# digital.net
KiCad netlist of a schematic drawn in EAGLE
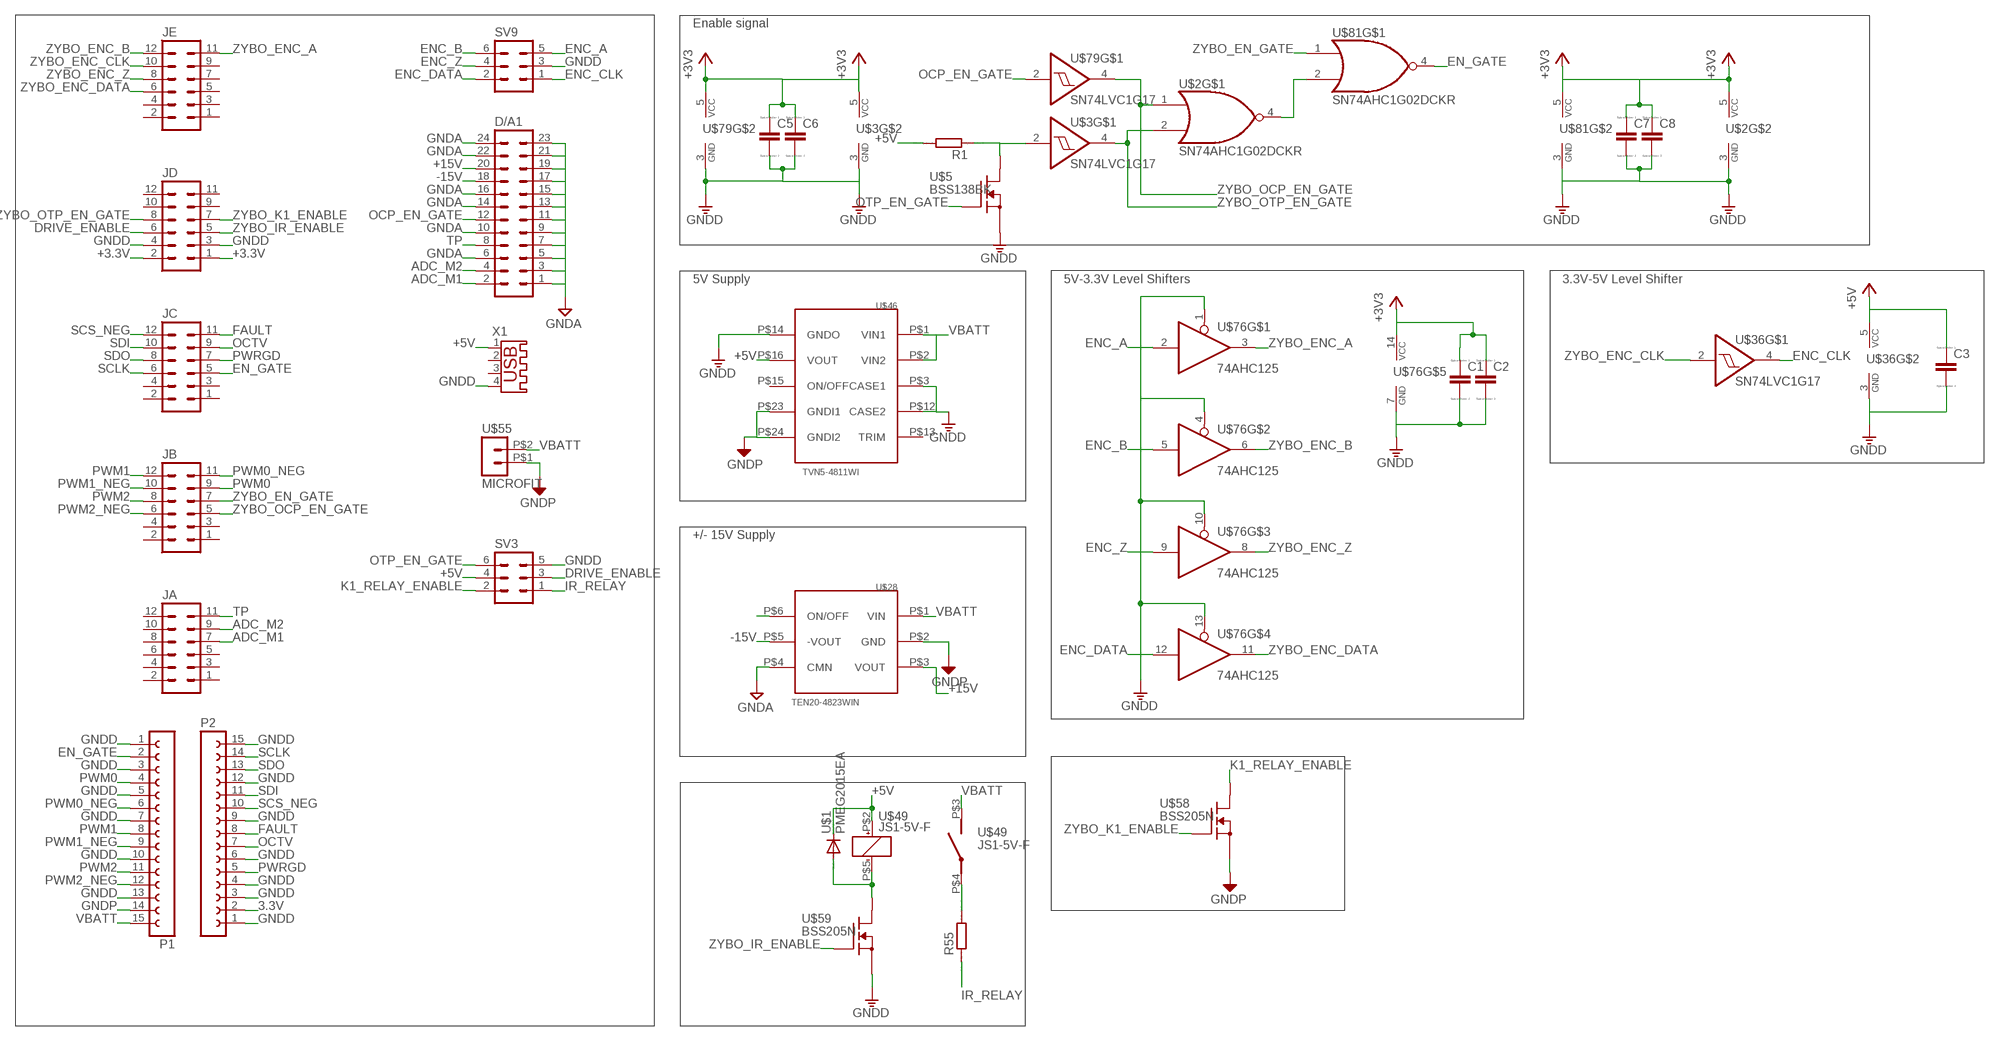
[diagram p0: schematic, sheet 1]

(export (version "E")
  (design (tool "Eeschema 10.0.6"))
  (components
    (comp (ref "C1")
      (value "CC1206")
      (footprint "eagle-import:C1206")
      (libsource (lib "eagle-import") (part "CC1206"))
    )
    (comp (ref "C2")
      (value "CC1206")
      (footprint "eagle-import:C1206")
      (libsource (lib "eagle-import") (part "CC1206"))
    )
    (comp (ref "C3")
      (value "CC1206")
      (footprint "eagle-import:C1206")
      (libsource (lib "eagle-import") (part "CC1206"))
    )
    (comp (ref "C5")
      (value "CC1206")
      (footprint "eagle-import:C1206")
      (libsource (lib "eagle-import") (part "CC1206"))
    )
    (comp (ref "C6")
      (value "CC1206")
      (footprint "eagle-import:C1206")
      (libsource (lib "eagle-import") (part "CC1206"))
    )
    (comp (ref "C7")
      (value "CC1206")
      (footprint "eagle-import:C1206")
      (libsource (lib "eagle-import") (part "CC1206"))
    )
    (comp (ref "C8")
      (value "CC1206")
      (footprint "eagle-import:C1206")
      (libsource (lib "eagle-import") (part "CC1206"))
    )
    (comp (ref "D/A1")
      (value "MA12-2")
      (footprint "eagle-import:MA12-2")
      (libsource (lib "eagle-import") (part "MA12-2"))
    )
    (comp (ref "JA")
      (value "MA06-2")
      (footprint "eagle-import:MA06-2")
      (libsource (lib "eagle-import") (part "MA06-2"))
    )
    (comp (ref "JB")
      (value "MA06-2")
      (footprint "eagle-import:MA06-2")
      (libsource (lib "eagle-import") (part "MA06-2"))
    )
    (comp (ref "JC")
      (value "MA06-2")
      (footprint "eagle-import:MA06-2")
      (libsource (lib "eagle-import") (part "MA06-2"))
    )
    (comp (ref "JD")
      (value "MA06-2")
      (footprint "eagle-import:MA06-2")
      (libsource (lib "eagle-import") (part "MA06-2"))
    )
    (comp (ref "JE")
      (value "MA06-2")
      (footprint "eagle-import:MA06-2")
      (libsource (lib "eagle-import") (part "MA06-2"))
    )
    (comp (ref "P1")
      (value "FE15-1")
      (footprint "eagle-import:FE15")
      (libsource (lib "eagle-import") (part "FE15-1"))
    )
    (comp (ref "P2")
      (value "FE15-1")
      (footprint "eagle-import:FE15")
      (libsource (lib "eagle-import") (part "FE15-1"))
    )
    (comp (ref "R1")
      (value "RR1206")
      (footprint "eagle-import:R1206")
      (libsource (lib "eagle-import") (part "RR1206"))
    )
    (comp (ref "R55")
      (value "RR1206")
      (footprint "eagle-import:R1206")
      (libsource (lib "eagle-import") (part "RR1206"))
    )
    (comp (ref "SV3")
      (value "MA03-2")
      (footprint "eagle-import:MA03-2")
      (libsource (lib "eagle-import") (part "MA03-2"))
    )
    (comp (ref "SV9")
      (value "MA03-2")
      (footprint "eagle-import:MA03-2")
      (libsource (lib "eagle-import") (part "MA03-2"))
    )
    (comp (ref "U$1")
      (value "PMEG2015EA")
      (footprint "eagle-import:SOD323_ST")
      (libsource (lib "eagle-import") (part "PMEG2015EA"))
    )
    (comp (ref "U$2")
      (value "SN74AHC1G02DCKR")
      (footprint "eagle-import:SOT23-5")
      (libsource (lib "eagle-import") (part "SN74AHC1G02DCKR"))
    )
    (comp (ref "U$3")
      (value "SN74LVC1G17")
      (footprint "eagle-import:SOT23-5L")
      (libsource (lib "eagle-import") (part "SN74LVC1G17"))
    )
    (comp (ref "U$5")
      (value "BSS138BK")
      (footprint "eagle-import:SOT23")
      (libsource (lib "eagle-import") (part "BSS138BK"))
    )
    (comp (ref "U$28")
      (value "TEN20-4823WIN")
      (footprint "eagle-import:TEN20-4823")
      (libsource (lib "eagle-import") (part "TEN20-4823WIN"))
    )
    (comp (ref "U$36")
      (value "SN74LVC1G17")
      (footprint "eagle-import:SOT23-5L")
      (libsource (lib "eagle-import") (part "SN74LVC1G17"))
    )
    (comp (ref "U$46")
      (value "TVN5-4811WI")
      (footprint "eagle-import:DIP24")
      (libsource (lib "eagle-import") (part "TVN5-4811WI"))
    )
    (comp (ref "U$49")
      (value "JS1-5V-F")
      (footprint "eagle-import:JS1-5V-F")
      (libsource (lib "eagle-import") (part "JS1-5V-F"))
    )
    (comp (ref "U$55")
      (value "MICROFIT")
      (footprint "eagle-import:MICROFIT-3.0")
      (libsource (lib "eagle-import") (part "MICROFIT"))
    )
    (comp (ref "U$58")
      (value "BSS205N")
      (footprint "eagle-import:SOT23")
      (libsource (lib "eagle-import") (part "BSS205N"))
    )
    (comp (ref "U$59")
      (value "BSS205N")
      (footprint "eagle-import:SOT23")
      (libsource (lib "eagle-import") (part "BSS205N"))
    )
    (comp (ref "U$76")
      (value "74AHC125")
      (footprint "eagle-import:SO14")
      (libsource (lib "eagle-import") (part "74AHC125"))
    )
    (comp (ref "U$79")
      (value "SN74LVC1G17")
      (footprint "eagle-import:SOT23-5L")
      (libsource (lib "eagle-import") (part "SN74LVC1G17"))
    )
    (comp (ref "U$81")
      (value "SN74AHC1G02DCKR")
      (footprint "eagle-import:SOT23-5")
      (libsource (lib "eagle-import") (part "SN74AHC1G02DCKR"))
    )
    (comp (ref "X1")
      (value "USB-A003")
      (footprint "eagle-import:USB-A003")
      (libsource (lib "eagle-import") (part "USB-A003"))
    )
  )
  (nets
    (net (code "1") (name "+3V3") (class "Default")
      (node (ref "C1") (pin "1") (pinfunction "1_1") (pintype "passive"))
      (node (ref "C2") (pin "1") (pinfunction "1_1") (pintype "passive"))
      (node (ref "C5") (pin "1") (pinfunction "1_1") (pintype "passive"))
      (node (ref "C6") (pin "1") (pinfunction "1_1") (pintype "passive"))
      (node (ref "C7") (pin "1") (pinfunction "1_1") (pintype "passive"))
      (node (ref "C8") (pin "1") (pinfunction "1_1") (pintype "passive"))
      (node (ref "U$2") (pin "5") (pinfunction "VCC_5") (pintype "power_in"))
      (node (ref "U$3") (pin "5") (pinfunction "VCC_5") (pintype "power_in"))
      (node (ref "U$76") (pin "14") (pinfunction "VCC_14") (pintype "power_in"))
      (node (ref "U$79") (pin "5") (pinfunction "VCC_5") (pintype "power_in"))
      (node (ref "U$81") (pin "5") (pinfunction "VCC_5") (pintype "power_in"))
    )
    (net (code "2") (name "+5V") (class "Default")
      (node (ref "C3") (pin "1") (pinfunction "1_1") (pintype "passive"))
      (node (ref "R1") (pin "2") (pinfunction "2_2") (pintype "passive"))
      (node (ref "SV3") (pin "4") (pinfunction "4_4") (pintype "passive"))
      (node (ref "U$1") (pin "C") (pinfunction "C_C") (pintype "passive"))
      (node (ref "U$36") (pin "5") (pinfunction "VCC_5") (pintype "power_in"))
      (node (ref "U$46") (pin "P$16") (pinfunction "VOUT_P$16") (pintype "bidirectional"))
      (node (ref "U$49") (pin "P$2") (pinfunction "+_P$2") (pintype "passive"))
      (node (ref "X1") (pin "1") (pinfunction "1_1") (pintype "passive"))
    )
    (net (code "3") (name "/+3.3V") (class "Default")
      (node (ref "JD") (pin "1") (pinfunction "1_1") (pintype "passive"))
      (node (ref "JD") (pin "2") (pinfunction "2_2") (pintype "passive"))
    )
    (net (code "4") (name "/+15V") (class "Default")
      (node (ref "D/A1") (pin "20") (pinfunction "20_20") (pintype "passive"))
      (node (ref "U$28") (pin "P$3") (pinfunction "VOUT_P$3") (pintype "bidirectional"))
    )
    (net (code "5") (name "/-15V") (class "Default")
      (node (ref "D/A1") (pin "18") (pinfunction "18_18") (pintype "passive"))
      (node (ref "U$28") (pin "P$5") (pinfunction "-VOUT_P$5") (pintype "bidirectional"))
    )
    (net (code "6") (name "/3.3V") (class "Default")
      (node (ref "P2") (pin "2") (pinfunction "2_2") (pintype "passive"))
    )
    (net (code "7") (name "/ADC_M1") (class "Default")
      (node (ref "D/A1") (pin "2") (pinfunction "2_2") (pintype "passive"))
      (node (ref "JA") (pin "7") (pinfunction "7_7") (pintype "passive"))
    )
    (net (code "8") (name "/ADC_M2") (class "Default")
      (node (ref "D/A1") (pin "4") (pinfunction "4_4") (pintype "passive"))
      (node (ref "JA") (pin "9") (pinfunction "9_9") (pintype "passive"))
    )
    (net (code "9") (name "/DRIVE_ENABLE") (class "Default")
      (node (ref "JD") (pin "6") (pinfunction "6_6") (pintype "passive"))
      (node (ref "SV3") (pin "3") (pinfunction "3_3") (pintype "passive"))
    )
    (net (code "10") (name "/ENC_A") (class "Default")
      (node (ref "SV9") (pin "5") (pinfunction "5_5") (pintype "passive"))
      (node (ref "U$76") (pin "2") (pinfunction "I_2") (pintype "input"))
    )
    (net (code "11") (name "/ENC_B") (class "Default")
      (node (ref "SV9") (pin "6") (pinfunction "6_6") (pintype "passive"))
      (node (ref "U$76") (pin "5") (pinfunction "I_5") (pintype "input"))
    )
    (net (code "12") (name "/ENC_CLK") (class "Default")
      (node (ref "SV9") (pin "1") (pinfunction "1_1") (pintype "passive"))
      (node (ref "U$36") (pin "4") (pinfunction "O_4") (pintype "output"))
    )
    (net (code "13") (name "/ENC_DATA") (class "Default")
      (node (ref "SV9") (pin "2") (pinfunction "2_2") (pintype "passive"))
      (node (ref "U$76") (pin "12") (pinfunction "I_12") (pintype "input"))
    )
    (net (code "14") (name "/ENC_Z") (class "Default")
      (node (ref "SV9") (pin "4") (pinfunction "4_4") (pintype "passive"))
      (node (ref "U$76") (pin "9") (pinfunction "I_9") (pintype "input"))
    )
    (net (code "15") (name "/EN_GATE") (class "Default")
      (node (ref "JC") (pin "5") (pinfunction "5_5") (pintype "passive"))
      (node (ref "P1") (pin "2") (pinfunction "2_2") (pintype "passive"))
      (node (ref "U$81") (pin "4") (pinfunction "O_4") (pintype "output"))
    )
    (net (code "16") (name "/FAULT") (class "Default")
      (node (ref "JC") (pin "11") (pinfunction "11_11") (pintype "passive"))
      (node (ref "P2") (pin "8") (pinfunction "8_8") (pintype "passive"))
    )
    (net (code "17") (name "/IR_RELAY") (class "Default")
      (node (ref "R55") (pin "1") (pinfunction "1_1") (pintype "passive"))
      (node (ref "SV3") (pin "1") (pinfunction "1_1") (pintype "passive"))
    )
    (net (code "18") (name "/K1_RELAY_ENABLE") (class "Default")
      (node (ref "SV3") (pin "2") (pinfunction "2_2") (pintype "passive"))
      (node (ref "U$58") (pin "3") (pinfunction "D_3") (pintype "passive"))
    )
    (net (code "19") (name "/OCP_EN_GATE") (class "Default")
      (node (ref "D/A1") (pin "12") (pinfunction "12_12") (pintype "passive"))
      (node (ref "U$79") (pin "2") (pinfunction "I_2") (pintype "input"))
    )
    (net (code "20") (name "/OCTV") (class "Default")
      (node (ref "JC") (pin "9") (pinfunction "9_9") (pintype "passive"))
      (node (ref "P2") (pin "7") (pinfunction "7_7") (pintype "passive"))
    )
    (net (code "21") (name "/OTP_EN_GATE") (class "Default")
      (node (ref "SV3") (pin "6") (pinfunction "6_6") (pintype "passive"))
      (node (ref "U$5") (pin "1") (pinfunction "G_1") (pintype "passive"))
    )
    (net (code "22") (name "/PWM0") (class "Default")
      (node (ref "JB") (pin "9") (pinfunction "9_9") (pintype "passive"))
      (node (ref "P1") (pin "4") (pinfunction "4_4") (pintype "passive"))
    )
    (net (code "23") (name "/PWM0_NEG") (class "Default")
      (node (ref "JB") (pin "11") (pinfunction "11_11") (pintype "passive"))
      (node (ref "P1") (pin "6") (pinfunction "6_6") (pintype "passive"))
    )
    (net (code "24") (name "/PWM1") (class "Default")
      (node (ref "JB") (pin "12") (pinfunction "12_12") (pintype "passive"))
      (node (ref "P1") (pin "8") (pinfunction "8_8") (pintype "passive"))
    )
    (net (code "25") (name "/PWM1_NEG") (class "Default")
      (node (ref "JB") (pin "10") (pinfunction "10_10") (pintype "passive"))
      (node (ref "P1") (pin "9") (pinfunction "9_9") (pintype "passive"))
    )
    (net (code "26") (name "/PWM2") (class "Default")
      (node (ref "JB") (pin "8") (pinfunction "8_8") (pintype "passive"))
      (node (ref "P1") (pin "11") (pinfunction "11_11") (pintype "passive"))
    )
    (net (code "27") (name "/PWM2_NEG") (class "Default")
      (node (ref "JB") (pin "6") (pinfunction "6_6") (pintype "passive"))
      (node (ref "P1") (pin "12") (pinfunction "12_12") (pintype "passive"))
    )
    (net (code "28") (name "/PWRGD") (class "Default")
      (node (ref "JC") (pin "7") (pinfunction "7_7") (pintype "passive"))
      (node (ref "P2") (pin "5") (pinfunction "5_5") (pintype "passive"))
    )
    (net (code "29") (name "/SCLK") (class "Default")
      (node (ref "JC") (pin "6") (pinfunction "6_6") (pintype "passive"))
      (node (ref "P2") (pin "14") (pinfunction "14_14") (pintype "passive"))
    )
    (net (code "30") (name "/SCS_NEG") (class "Default")
      (node (ref "JC") (pin "12") (pinfunction "12_12") (pintype "passive"))
      (node (ref "P2") (pin "10") (pinfunction "10_10") (pintype "passive"))
    )
    (net (code "31") (name "/SDI") (class "Default")
      (node (ref "JC") (pin "10") (pinfunction "10_10") (pintype "passive"))
      (node (ref "P2") (pin "11") (pinfunction "11_11") (pintype "passive"))
    )
    (net (code "32") (name "/SDO") (class "Default")
      (node (ref "JC") (pin "8") (pinfunction "8_8") (pintype "passive"))
      (node (ref "P2") (pin "13") (pinfunction "13_13") (pintype "passive"))
    )
    (net (code "33") (name "/TP") (class "Default")
      (node (ref "D/A1") (pin "8") (pinfunction "8_8") (pintype "passive"))
      (node (ref "JA") (pin "11") (pinfunction "11_11") (pintype "passive"))
    )
    (net (code "34") (name "/VBATT") (class "Default")
      (node (ref "P1") (pin "15") (pinfunction "15_15") (pintype "passive"))
      (node (ref "U$28") (pin "P$1") (pinfunction "VIN_P$1") (pintype "bidirectional"))
      (node (ref "U$46") (pin "P$1") (pinfunction "VIN1_P$1") (pintype "bidirectional"))
      (node (ref "U$46") (pin "P$2") (pinfunction "VIN2_P$2") (pintype "bidirectional"))
      (node (ref "U$49") (pin "P$3") (pinfunction "S_P$3") (pintype "passive"))
      (node (ref "U$55") (pin "P$2") (pinfunction "3_P$2") (pintype "passive"))
    )
    (net (code "35") (name "/ZYBO_ENC_A") (class "Default")
      (node (ref "JE") (pin "11") (pinfunction "11_11") (pintype "passive"))
      (node (ref "U$76") (pin "3") (pinfunction "O_3") (pintype "tri_state"))
    )
    (net (code "36") (name "/ZYBO_ENC_B") (class "Default")
      (node (ref "JE") (pin "12") (pinfunction "12_12") (pintype "passive"))
      (node (ref "U$76") (pin "6") (pinfunction "O_6") (pintype "tri_state"))
    )
    (net (code "37") (name "/ZYBO_ENC_CLK") (class "Default")
      (node (ref "JE") (pin "10") (pinfunction "10_10") (pintype "passive"))
      (node (ref "U$36") (pin "2") (pinfunction "I_2") (pintype "input"))
    )
    (net (code "38") (name "/ZYBO_ENC_DATA") (class "Default")
      (node (ref "JE") (pin "6") (pinfunction "6_6") (pintype "passive"))
      (node (ref "U$76") (pin "11") (pinfunction "O_11") (pintype "tri_state"))
    )
    (net (code "39") (name "/ZYBO_ENC_Z") (class "Default")
      (node (ref "JE") (pin "8") (pinfunction "8_8") (pintype "passive"))
      (node (ref "U$76") (pin "8") (pinfunction "O_8") (pintype "tri_state"))
    )
    (net (code "40") (name "/ZYBO_EN_GATE") (class "Default")
      (node (ref "JB") (pin "7") (pinfunction "7_7") (pintype "passive"))
      (node (ref "U$81") (pin "1") (pinfunction "I0_1") (pintype "input"))
    )
    (net (code "41") (name "/ZYBO_IR_ENABLE") (class "Default")
      (node (ref "JD") (pin "5") (pinfunction "5_5") (pintype "passive"))
      (node (ref "U$59") (pin "1") (pinfunction "G_1") (pintype "passive"))
    )
    (net (code "42") (name "/ZYBO_K1_ENABLE") (class "Default")
      (node (ref "JD") (pin "7") (pinfunction "7_7") (pintype "passive"))
      (node (ref "U$58") (pin "1") (pinfunction "G_1") (pintype "passive"))
    )
    (net (code "43") (name "/ZYBO_OCP_EN_GATE") (class "Default")
      (node (ref "JB") (pin "5") (pinfunction "5_5") (pintype "passive"))
      (node (ref "U$2") (pin "1") (pinfunction "I0_1") (pintype "input"))
      (node (ref "U$79") (pin "4") (pinfunction "O_4") (pintype "output"))
    )
    (net (code "44") (name "/ZYBO_OTP_EN_GATE") (class "Default")
      (node (ref "JD") (pin "8") (pinfunction "8_8") (pintype "passive"))
      (node (ref "U$2") (pin "2") (pinfunction "I1_2") (pintype "input"))
      (node (ref "U$3") (pin "4") (pinfunction "O_4") (pintype "output"))
    )
    (net (code "45") (name "GNDA") (class "Default")
      (node (ref "D/A1") (pin "1") (pinfunction "1_1") (pintype "passive"))
      (node (ref "D/A1") (pin "10") (pinfunction "10_10") (pintype "passive"))
      (node (ref "D/A1") (pin "11") (pinfunction "11_11") (pintype "passive"))
      (node (ref "D/A1") (pin "13") (pinfunction "13_13") (pintype "passive"))
      (node (ref "D/A1") (pin "14") (pinfunction "14_14") (pintype "passive"))
      (node (ref "D/A1") (pin "15") (pinfunction "15_15") (pintype "passive"))
      (node (ref "D/A1") (pin "16") (pinfunction "16_16") (pintype "passive"))
      (node (ref "D/A1") (pin "22") (pinfunction "22_22") (pintype "passive"))
      (node (ref "D/A1") (pin "23") (pinfunction "23_23") (pintype "passive"))
      (node (ref "D/A1") (pin "24") (pinfunction "24_24") (pintype "passive"))
      (node (ref "D/A1") (pin "3") (pinfunction "3_3") (pintype "passive"))
      (node (ref "D/A1") (pin "5") (pinfunction "5_5") (pintype "passive"))
      (node (ref "D/A1") (pin "6") (pinfunction "6_6") (pintype "passive"))
      (node (ref "D/A1") (pin "7") (pinfunction "7_7") (pintype "passive"))
      (node (ref "D/A1") (pin "9") (pinfunction "9_9") (pintype "passive"))
      (node (ref "U$28") (pin "P$4") (pinfunction "CMN_P$4") (pintype "bidirectional"))
    )
    (net (code "46") (name "GNDD") (class "Default")
      (node (ref "C1") (pin "2") (pinfunction "2_2") (pintype "passive"))
      (node (ref "C2") (pin "2") (pinfunction "2_2") (pintype "passive"))
      (node (ref "C3") (pin "2") (pinfunction "2_2") (pintype "passive"))
      (node (ref "C5") (pin "2") (pinfunction "2_2") (pintype "passive"))
      (node (ref "C6") (pin "2") (pinfunction "2_2") (pintype "passive"))
      (node (ref "C7") (pin "2") (pinfunction "2_2") (pintype "passive"))
      (node (ref "C8") (pin "2") (pinfunction "2_2") (pintype "passive"))
      (node (ref "JD") (pin "3") (pinfunction "3_3") (pintype "passive"))
      (node (ref "JD") (pin "4") (pinfunction "4_4") (pintype "passive"))
      (node (ref "P1") (pin "1") (pinfunction "1_1") (pintype "passive"))
      (node (ref "P1") (pin "10") (pinfunction "10_10") (pintype "passive"))
      (node (ref "P1") (pin "13") (pinfunction "13_13") (pintype "passive"))
      (node (ref "P1") (pin "3") (pinfunction "3_3") (pintype "passive"))
      (node (ref "P1") (pin "5") (pinfunction "5_5") (pintype "passive"))
      (node (ref "P1") (pin "7") (pinfunction "7_7") (pintype "passive"))
      (node (ref "P2") (pin "1") (pinfunction "1_1") (pintype "passive"))
      (node (ref "P2") (pin "12") (pinfunction "12_12") (pintype "passive"))
      (node (ref "P2") (pin "15") (pinfunction "15_15") (pintype "passive"))
      (node (ref "P2") (pin "3") (pinfunction "3_3") (pintype "passive"))
      (node (ref "P2") (pin "4") (pinfunction "4_4") (pintype "passive"))
      (node (ref "P2") (pin "6") (pinfunction "6_6") (pintype "passive"))
      (node (ref "P2") (pin "9") (pinfunction "9_9") (pintype "passive"))
      (node (ref "SV3") (pin "5") (pinfunction "5_5") (pintype "passive"))
      (node (ref "SV9") (pin "3") (pinfunction "3_3") (pintype "passive"))
      (node (ref "U$2") (pin "3") (pinfunction "GND_3") (pintype "power_in"))
      (node (ref "U$3") (pin "3") (pinfunction "GND_3") (pintype "power_in"))
      (node (ref "U$36") (pin "3") (pinfunction "GND_3") (pintype "power_in"))
      (node (ref "U$46") (pin "P$12") (pinfunction "CASE2_P$12") (pintype "bidirectional"))
      (node (ref "U$46") (pin "P$14") (pinfunction "GNDO_P$14") (pintype "bidirectional"))
      (node (ref "U$46") (pin "P$3") (pinfunction "CASE1_P$3") (pintype "bidirectional"))
      (node (ref "U$5") (pin "2") (pinfunction "S_2") (pintype "passive"))
      (node (ref "U$59") (pin "2") (pinfunction "S_2") (pintype "passive"))
      (node (ref "U$76") (pin "1") (pinfunction "OE_1") (pintype "input"))
      (node (ref "U$76") (pin "10") (pinfunction "OE_10") (pintype "input"))
      (node (ref "U$76") (pin "13") (pinfunction "OE_13") (pintype "input"))
      (node (ref "U$76") (pin "4") (pinfunction "OE_4") (pintype "input"))
      (node (ref "U$76") (pin "7") (pinfunction "GND_7") (pintype "power_in"))
      (node (ref "U$79") (pin "3") (pinfunction "GND_3") (pintype "power_in"))
      (node (ref "U$81") (pin "3") (pinfunction "GND_3") (pintype "power_in"))
      (node (ref "X1") (pin "4") (pinfunction "4_4") (pintype "passive"))
    )
    (net (code "47") (name "GNDP") (class "Default")
      (node (ref "P1") (pin "14") (pinfunction "14_14") (pintype "passive"))
      (node (ref "U$28") (pin "P$2") (pinfunction "GND_P$2") (pintype "bidirectional"))
      (node (ref "U$46") (pin "P$23") (pinfunction "GNDI1_P$23") (pintype "bidirectional"))
      (node (ref "U$46") (pin "P$24") (pinfunction "GNDI2_P$24") (pintype "bidirectional"))
      (node (ref "U$55") (pin "P$1") (pinfunction "2_P$1") (pintype "passive"))
      (node (ref "U$58") (pin "2") (pinfunction "S_2") (pintype "passive"))
    )
    (net (code "48") (name "Net-(U$2A-O)") (class "Default")
      (node (ref "U$2") (pin "4") (pinfunction "O_4") (pintype "output"))
      (node (ref "U$81") (pin "2") (pinfunction "I1_2") (pintype "input"))
    )
    (net (code "49") (name "Net-(U$3A-I)") (class "Default")
      (node (ref "R1") (pin "1") (pinfunction "1_1") (pintype "passive"))
      (node (ref "U$3") (pin "2") (pinfunction "I_2") (pintype "input"))
      (node (ref "U$5") (pin "3") (pinfunction "D_3") (pintype "passive"))
    )
    (net (code "50") (name "Net-(U$49A--)") (class "Default")
      (node (ref "U$1") (pin "A") (pinfunction "A_A") (pintype "passive"))
      (node (ref "U$49") (pin "P$5") (pinfunction "-_P$5") (pintype "passive"))
      (node (ref "U$59") (pin "3") (pinfunction "D_3") (pintype "passive"))
    )
    (net (code "51") (name "Net-(U$49B-P)") (class "Default")
      (node (ref "R55") (pin "2") (pinfunction "2_2") (pintype "passive"))
      (node (ref "U$49") (pin "P$4") (pinfunction "P_P$4") (pintype "passive"))
    )
    (net (code "52") (name "unconnected-(D/A1-Pad17)") (class "Default")
      (node (ref "D/A1") (pin "17") (pinfunction "17_17") (pintype "passive"))
    )
    (net (code "53") (name "unconnected-(D/A1-Pad19)") (class "Default")
      (node (ref "D/A1") (pin "19") (pinfunction "19_19") (pintype "passive"))
    )
    (net (code "54") (name "unconnected-(D/A1-Pad21)") (class "Default")
      (node (ref "D/A1") (pin "21") (pinfunction "21_21") (pintype "passive"))
    )
    (net (code "55") (name "unconnected-(JA-Pad1)") (class "Default")
      (node (ref "JA") (pin "1") (pinfunction "1_1") (pintype "passive"))
    )
    (net (code "56") (name "unconnected-(JA-Pad2)") (class "Default")
      (node (ref "JA") (pin "2") (pinfunction "2_2") (pintype "passive"))
    )
    (net (code "57") (name "unconnected-(JA-Pad3)") (class "Default")
      (node (ref "JA") (pin "3") (pinfunction "3_3") (pintype "passive"))
    )
    (net (code "58") (name "unconnected-(JA-Pad4)") (class "Default")
      (node (ref "JA") (pin "4") (pinfunction "4_4") (pintype "passive"))
    )
    (net (code "59") (name "unconnected-(JA-Pad5)") (class "Default")
      (node (ref "JA") (pin "5") (pinfunction "5_5") (pintype "passive"))
    )
    (net (code "60") (name "unconnected-(JA-Pad6)") (class "Default")
      (node (ref "JA") (pin "6") (pinfunction "6_6") (pintype "passive"))
    )
    (net (code "61") (name "unconnected-(JA-Pad8)") (class "Default")
      (node (ref "JA") (pin "8") (pinfunction "8_8") (pintype "passive"))
    )
    (net (code "62") (name "unconnected-(JA-Pad10)") (class "Default")
      (node (ref "JA") (pin "10") (pinfunction "10_10") (pintype "passive"))
    )
    (net (code "63") (name "unconnected-(JA-Pad12)") (class "Default")
      (node (ref "JA") (pin "12") (pinfunction "12_12") (pintype "passive"))
    )
    (net (code "64") (name "unconnected-(JB-Pad1)") (class "Default")
      (node (ref "JB") (pin "1") (pinfunction "1_1") (pintype "passive"))
    )
    (net (code "65") (name "unconnected-(JB-Pad2)") (class "Default")
      (node (ref "JB") (pin "2") (pinfunction "2_2") (pintype "passive"))
    )
    (net (code "66") (name "unconnected-(JB-Pad3)") (class "Default")
      (node (ref "JB") (pin "3") (pinfunction "3_3") (pintype "passive"))
    )
    (net (code "67") (name "unconnected-(JB-Pad4)") (class "Default")
      (node (ref "JB") (pin "4") (pinfunction "4_4") (pintype "passive"))
    )
    (net (code "68") (name "unconnected-(JC-Pad1)") (class "Default")
      (node (ref "JC") (pin "1") (pinfunction "1_1") (pintype "passive"))
    )
    (net (code "69") (name "unconnected-(JC-Pad2)") (class "Default")
      (node (ref "JC") (pin "2") (pinfunction "2_2") (pintype "passive"))
    )
    (net (code "70") (name "unconnected-(JC-Pad3)") (class "Default")
      (node (ref "JC") (pin "3") (pinfunction "3_3") (pintype "passive"))
    )
    (net (code "71") (name "unconnected-(JC-Pad4)") (class "Default")
      (node (ref "JC") (pin "4") (pinfunction "4_4") (pintype "passive"))
    )
    (net (code "72") (name "unconnected-(JD-Pad9)") (class "Default")
      (node (ref "JD") (pin "9") (pinfunction "9_9") (pintype "passive"))
    )
    (net (code "73") (name "unconnected-(JD-Pad10)") (class "Default")
      (node (ref "JD") (pin "10") (pinfunction "10_10") (pintype "passive"))
    )
    (net (code "74") (name "unconnected-(JD-Pad11)") (class "Default")
      (node (ref "JD") (pin "11") (pinfunction "11_11") (pintype "passive"))
    )
    (net (code "75") (name "unconnected-(JD-Pad12)") (class "Default")
      (node (ref "JD") (pin "12") (pinfunction "12_12") (pintype "passive"))
    )
    (net (code "76") (name "unconnected-(JE-Pad1)") (class "Default")
      (node (ref "JE") (pin "1") (pinfunction "1_1") (pintype "passive"))
    )
    (net (code "77") (name "unconnected-(JE-Pad2)") (class "Default")
      (node (ref "JE") (pin "2") (pinfunction "2_2") (pintype "passive"))
    )
    (net (code "78") (name "unconnected-(JE-Pad3)") (class "Default")
      (node (ref "JE") (pin "3") (pinfunction "3_3") (pintype "passive"))
    )
    (net (code "79") (name "unconnected-(JE-Pad4)") (class "Default")
      (node (ref "JE") (pin "4") (pinfunction "4_4") (pintype "passive"))
    )
    (net (code "80") (name "unconnected-(JE-Pad5)") (class "Default")
      (node (ref "JE") (pin "5") (pinfunction "5_5") (pintype "passive"))
    )
    (net (code "81") (name "unconnected-(JE-Pad7)") (class "Default")
      (node (ref "JE") (pin "7") (pinfunction "7_7") (pintype "passive"))
    )
    (net (code "82") (name "unconnected-(JE-Pad9)") (class "Default")
      (node (ref "JE") (pin "9") (pinfunction "9_9") (pintype "passive"))
    )
    (net (code "83") (name "unconnected-(U$28-ON{slash}OFF-PadP$6)") (class "Default")
      (node (ref "U$28") (pin "P$6") (pinfunction "ON/OFF_P$6") (pintype "bidirectional"))
    )
    (net (code "84") (name "unconnected-(U$46-ON{slash}OFF-PadP$15)") (class "Default")
      (node (ref "U$46") (pin "P$15") (pinfunction "ON/OFF_P$15") (pintype "bidirectional"))
    )
    (net (code "85") (name "unconnected-(U$46-TRIM-PadP$13)") (class "Default")
      (node (ref "U$46") (pin "P$13") (pinfunction "TRIM_P$13") (pintype "bidirectional"))
    )
    (net (code "86") (name "unconnected-(X1-Pad2)") (class "Default")
      (node (ref "X1") (pin "2") (pinfunction "2_2") (pintype "passive"))
    )
    (net (code "87") (name "unconnected-(X1-Pad3)") (class "Default")
      (node (ref "X1") (pin "3") (pinfunction "3_3") (pintype "passive"))
    )
  )
)
